# ESP8266-DS18B20-lite.net
KiCad netlist of a schematic drawn in EAGLE
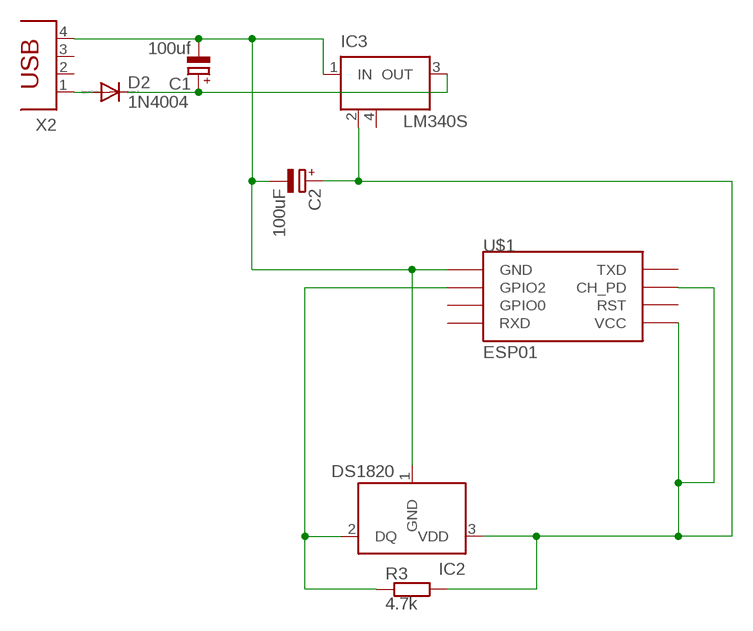
[diagram p0: schematic, sheet 1]

(export (version "E")
  (design (tool "Eeschema 10.0.6"))
  (components
    (comp (ref "C1")
      (value "100uf")
      (footprint "eagle-import:E2,5-5")
      (libsource (lib "eagle-import") (part "CPOL-EUE2.5-5"))
    )
    (comp (ref "C2")
      (value "100uF")
      (footprint "eagle-import:E2,5-5")
      (libsource (lib "eagle-import") (part "CPOL-EUE2.5-5"))
    )
    (comp (ref "D2")
      (value "1N4004")
      (footprint "eagle-import:DO41-10")
      (libsource (lib "eagle-import") (part "1N4004"))
    )
    (comp (ref "IC2")
      (value "DS1820")
      (footprint "eagle-import:TO-92")
      (libsource (lib "eagle-import") (part "DS1820"))
    )
    (comp (ref "IC3")
      (value "LM340S")
      (footprint "eagle-import:SOT223")
      (libsource (lib "eagle-import") (part "LM340S"))
    )
    (comp (ref "R3")
      (value "4.7k")
      (footprint "eagle-import:SMK")
      (libsource (lib "eagle-import") (part "SMK"))
    )
    (comp (ref "U$1")
      (value "ESP01")
      (footprint "eagle-import:ESP01")
      (libsource (lib "eagle-import") (part "ESP01"))
    )
    (comp (ref "X2")
      (value "PN61729")
      (footprint "eagle-import:PN61729")
      (libsource (lib "eagle-import") (part "PN61729"))
    )
  )
  (nets
    (net (code "1") (name "/5V") (class "Default")
      (node (ref "C1") (pin "+") (pinfunction "+_+") (pintype "passive"))
      (node (ref "D2") (pin "A") (pinfunction "A_A") (pintype "passive"))
      (node (ref "D2") (pin "C") (pinfunction "C_C") (pintype "passive"))
      (node (ref "IC3") (pin "3") (pinfunction "OUT_3") (pintype "passive"))
      (node (ref "X2") (pin "1") (pinfunction "1_1") (pintype "passive"))
    )
    (net (code "2") (name "/GND") (class "Default")
      (node (ref "IC3") (pin "4") (pinfunction "GND_4") (pintype "power_in"))
    )
    (net (code "3") (name "Net-(IC2-DQ)") (class "Default")
      (node (ref "IC2") (pin "2") (pinfunction "DQ_2") (pintype "output"))
      (node (ref "R3") (pin "2") (pinfunction "2_2") (pintype "passive"))
      (node (ref "U$1") (pin "GPIO2") (pinfunction "GPIO2_GPIO2") (pintype "bidirectional"))
    )
    (net (code "4") (name "Net-(IC2-GND)") (class "Default")
      (node (ref "C1") (pin "-") (pinfunction "-_-") (pintype "passive"))
      (node (ref "C2") (pin "-") (pinfunction "-_-") (pintype "passive"))
      (node (ref "IC2") (pin "1") (pinfunction "GND_1") (pintype "power_in"))
      (node (ref "IC3") (pin "1") (pinfunction "IN_1") (pintype "input"))
      (node (ref "U$1") (pin "GND") (pinfunction "GND_GND") (pintype "bidirectional"))
      (node (ref "X2") (pin "4") (pinfunction "4_4") (pintype "passive"))
    )
    (net (code "5") (name "Net-(IC2-VDD)") (class "Default")
      (node (ref "C2") (pin "+") (pinfunction "+_+") (pintype "passive"))
      (node (ref "IC2") (pin "3") (pinfunction "VDD_3") (pintype "input"))
      (node (ref "IC3") (pin "2") (pinfunction "GND_2") (pintype "power_in"))
      (node (ref "R3") (pin "1") (pinfunction "1_1") (pintype "passive"))
      (node (ref "U$1") (pin "CH_PD") (pinfunction "CH_PD_CH_PD") (pintype "bidirectional"))
      (node (ref "U$1") (pin "VCC") (pinfunction "VCC_VCC") (pintype "bidirectional"))
    )
    (net (code "6") (name "unconnected-(U$1-PadGPIO0)") (class "Default")
      (node (ref "U$1") (pin "GPIO0") (pinfunction "GPIO0_GPIO0") (pintype "bidirectional"))
    )
    (net (code "7") (name "unconnected-(U$1-PadRST)") (class "Default")
      (node (ref "U$1") (pin "RST") (pinfunction "RST_RST") (pintype "bidirectional"))
    )
    (net (code "8") (name "unconnected-(U$1-RXD-PadRX)") (class "Default")
      (node (ref "U$1") (pin "RX") (pinfunction "RXD_RX") (pintype "bidirectional"))
    )
    (net (code "9") (name "unconnected-(U$1-TXD-PadTX)") (class "Default")
      (node (ref "U$1") (pin "TX") (pinfunction "TXD_TX") (pintype "bidirectional"))
    )
    (net (code "10") (name "unconnected-(X2-Pad2)") (class "Default")
      (node (ref "X2") (pin "2") (pinfunction "2_2") (pintype "passive"))
    )
    (net (code "11") (name "unconnected-(X2-Pad3)") (class "Default")
      (node (ref "X2") (pin "3") (pinfunction "3_3") (pintype "passive"))
    )
  )
)
